# tiny85-uvlp-hw.net
KiCad netlist of a schematic drawn in EAGLE
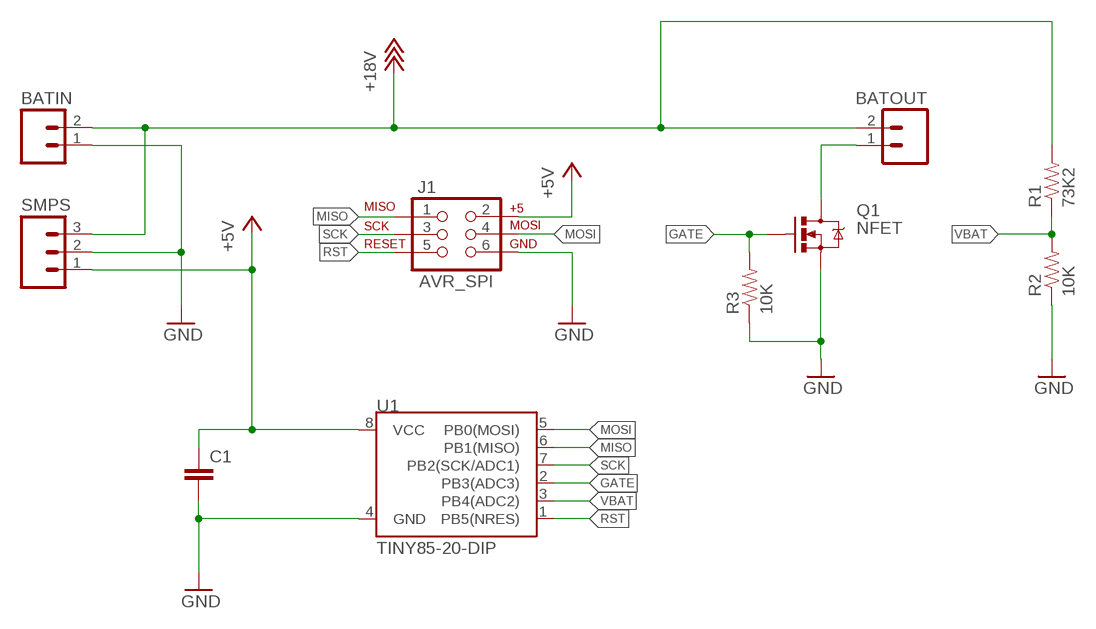
[diagram p0: schematic, sheet 1]

(export (version "E")
  (design (tool "Eeschema 10.0.6"))
  (components
    (comp (ref "BATIN")
      (value "M02PTH3")
      (footprint "eagle-import:1X02_LONGPADS")
      (libsource (lib "eagle-import") (part "M02PTH3"))
    )
    (comp (ref "BATOUT")
      (value "M02PTH3")
      (footprint "eagle-import:1X02_LONGPADS")
      (libsource (lib "eagle-import") (part "M02PTH3"))
    )
    (comp (ref "C1")
      (value "0.1UF-50V-20%(PTH)KIT-EZ")
      (footprint "eagle-import:CAP-PTH-SMALL-KIT")
      (libsource (lib "eagle-import") (part "0.1UF-50V-20%(PTH)KIT-EZ"))
    )
    (comp (ref "J1")
      (value "AVR_SPI")
      (footprint "eagle-import:2X3")
      (libsource (lib "eagle-import") (part "AVR_SPI_PRG_6PTH"))
    )
    (comp (ref "Q1")
      (value "NFET")
      (footprint "eagle-import:TO220V")
      (libsource (lib "eagle-import") (part "MOSFET-NCHANNELFQP30N06L"))
    )
    (comp (ref "R1")
      (value "73K2")
      (footprint "eagle-import:AXIAL-0.3")
      (libsource (lib "eagle-import") (part "RESISTORAXIAL-0.3"))
    )
    (comp (ref "R2")
      (value "10K")
      (footprint "eagle-import:AXIAL-0.3")
      (libsource (lib "eagle-import") (part "RESISTORAXIAL-0.3"))
    )
    (comp (ref "R3")
      (value "10K")
      (footprint "eagle-import:AXIAL-0.3")
      (libsource (lib "eagle-import") (part "RESISTORAXIAL-0.3"))
    )
    (comp (ref "SMPS")
      (value "M03LONGPADS")
      (footprint "eagle-import:1X03_LONGPADS")
      (libsource (lib "eagle-import") (part "M03LONGPADS"))
    )
    (comp (ref "U1")
      (value "TINY85-20-DIP")
      (footprint "eagle-import:DIP08")
      (libsource (lib "eagle-import") (part "ATTINY45TINY85-20-DIP"))
    )
  )
  (nets
    (net (code "1") (name "+5V") (class "Default")
      (node (ref "C1") (pin "1") (pinfunction "1_1") (pintype "passive"))
      (node (ref "J1") (pin "2") (pinfunction "2_2") (pintype "passive"))
      (node (ref "SMPS") (pin "1") (pinfunction "1_1") (pintype "passive"))
      (node (ref "U1") (pin "8") (pinfunction "VCC_8") (pintype "bidirectional"))
    )
    (net (code "2") (name "+18V") (class "Default")
      (node (ref "BATIN") (pin "2") (pinfunction "2_2") (pintype "passive"))
      (node (ref "BATOUT") (pin "2") (pinfunction "2_2") (pintype "passive"))
      (node (ref "R1") (pin "P$2") (pinfunction "2_P$2") (pintype "passive"))
      (node (ref "SMPS") (pin "3") (pinfunction "3_3") (pintype "passive"))
    )
    (net (code "3") (name "GATE") (class "Default")
      (node (ref "Q1") (pin "1") (pinfunction "G_1") (pintype "passive"))
      (node (ref "R3") (pin "P$2") (pinfunction "2_P$2") (pintype "passive"))
      (node (ref "U1") (pin "2") (pinfunction "PB3(ADC3)_2") (pintype "bidirectional"))
    )
    (net (code "4") (name "GND") (class "Default")
      (node (ref "BATIN") (pin "1") (pinfunction "1_1") (pintype "passive"))
      (node (ref "C1") (pin "2") (pinfunction "2_2") (pintype "passive"))
      (node (ref "J1") (pin "6") (pinfunction "6_6") (pintype "passive"))
      (node (ref "Q1") (pin "3") (pinfunction "S_3") (pintype "passive"))
      (node (ref "R2") (pin "P$1") (pinfunction "1_P$1") (pintype "passive"))
      (node (ref "R3") (pin "P$1") (pinfunction "1_P$1") (pintype "passive"))
      (node (ref "SMPS") (pin "2") (pinfunction "2_2") (pintype "passive"))
      (node (ref "U1") (pin "4") (pinfunction "GND_4") (pintype "bidirectional"))
    )
    (net (code "5") (name "MISO") (class "Default")
      (node (ref "J1") (pin "1") (pinfunction "1_1") (pintype "passive"))
      (node (ref "U1") (pin "6") (pinfunction "PB1(MISO)_6") (pintype "bidirectional"))
    )
    (net (code "6") (name "MOSI") (class "Default")
      (node (ref "J1") (pin "4") (pinfunction "4_4") (pintype "passive"))
      (node (ref "U1") (pin "5") (pinfunction "PB0(MOSI)_5") (pintype "bidirectional"))
    )
    (net (code "7") (name "Net-(Q1-D)") (class "Default")
      (node (ref "BATOUT") (pin "1") (pinfunction "1_1") (pintype "passive"))
      (node (ref "Q1") (pin "2") (pinfunction "D_2") (pintype "passive"))
    )
    (net (code "8") (name "RST") (class "Default")
      (node (ref "J1") (pin "5") (pinfunction "5_5") (pintype "passive"))
      (node (ref "U1") (pin "1") (pinfunction "PB5(NRES)_1") (pintype "bidirectional"))
    )
    (net (code "9") (name "SCK") (class "Default")
      (node (ref "J1") (pin "3") (pinfunction "3_3") (pintype "passive"))
      (node (ref "U1") (pin "7") (pinfunction "PB2(SCK/ADC1)_7") (pintype "bidirectional"))
    )
    (net (code "10") (name "VBAT") (class "Default")
      (node (ref "R1") (pin "P$1") (pinfunction "1_P$1") (pintype "passive"))
      (node (ref "R2") (pin "P$2") (pinfunction "2_P$2") (pintype "passive"))
      (node (ref "U1") (pin "3") (pinfunction "PB4(ADC2)_3") (pintype "bidirectional"))
    )
  )
)
